# Controller.net
KiCad netlist of a schematic drawn in Altium Designer
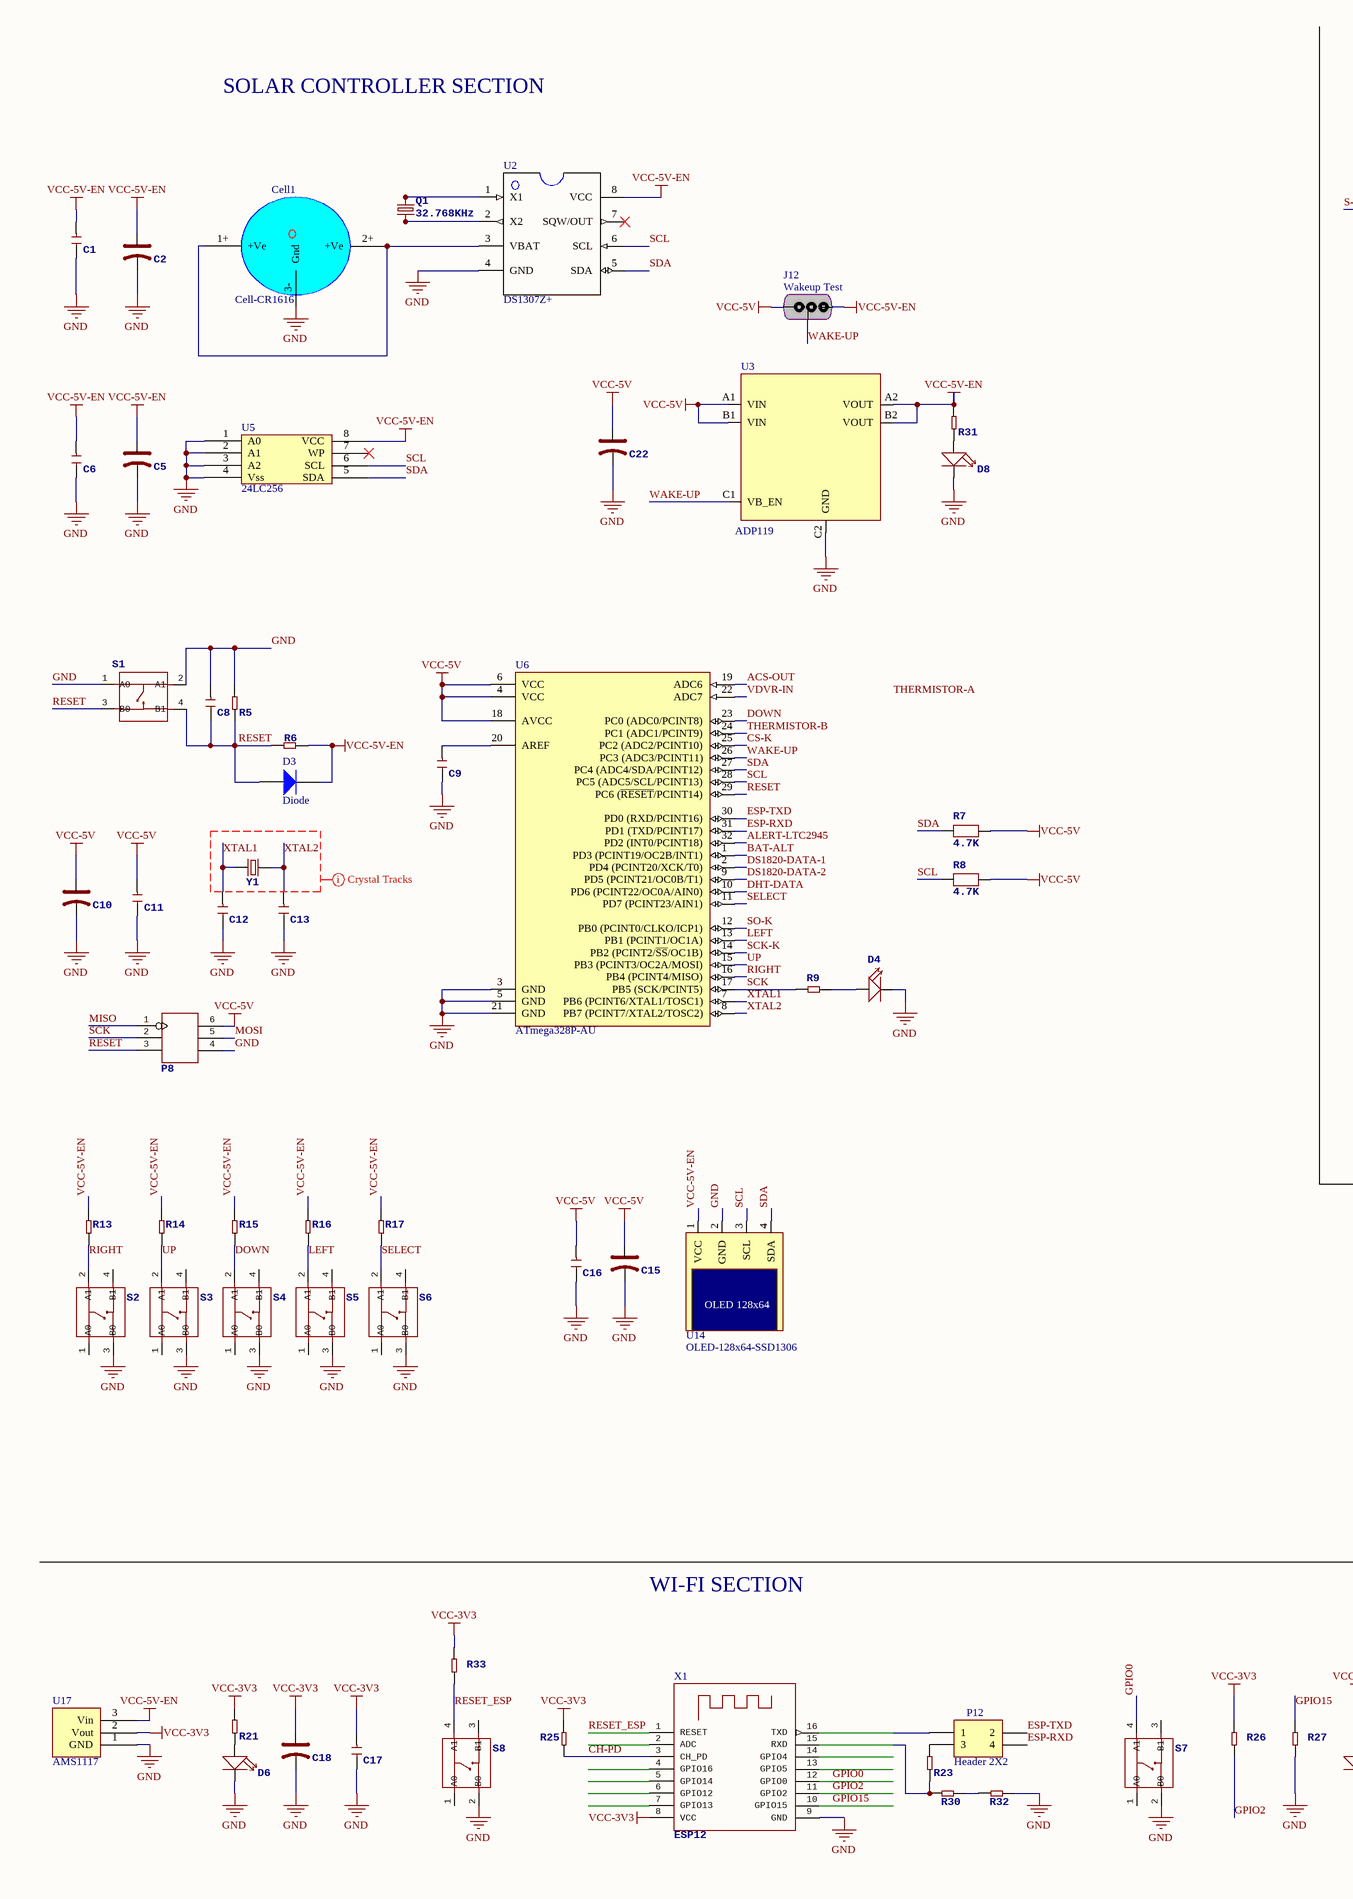
[diagram p0: Controller.SchDoc, left]
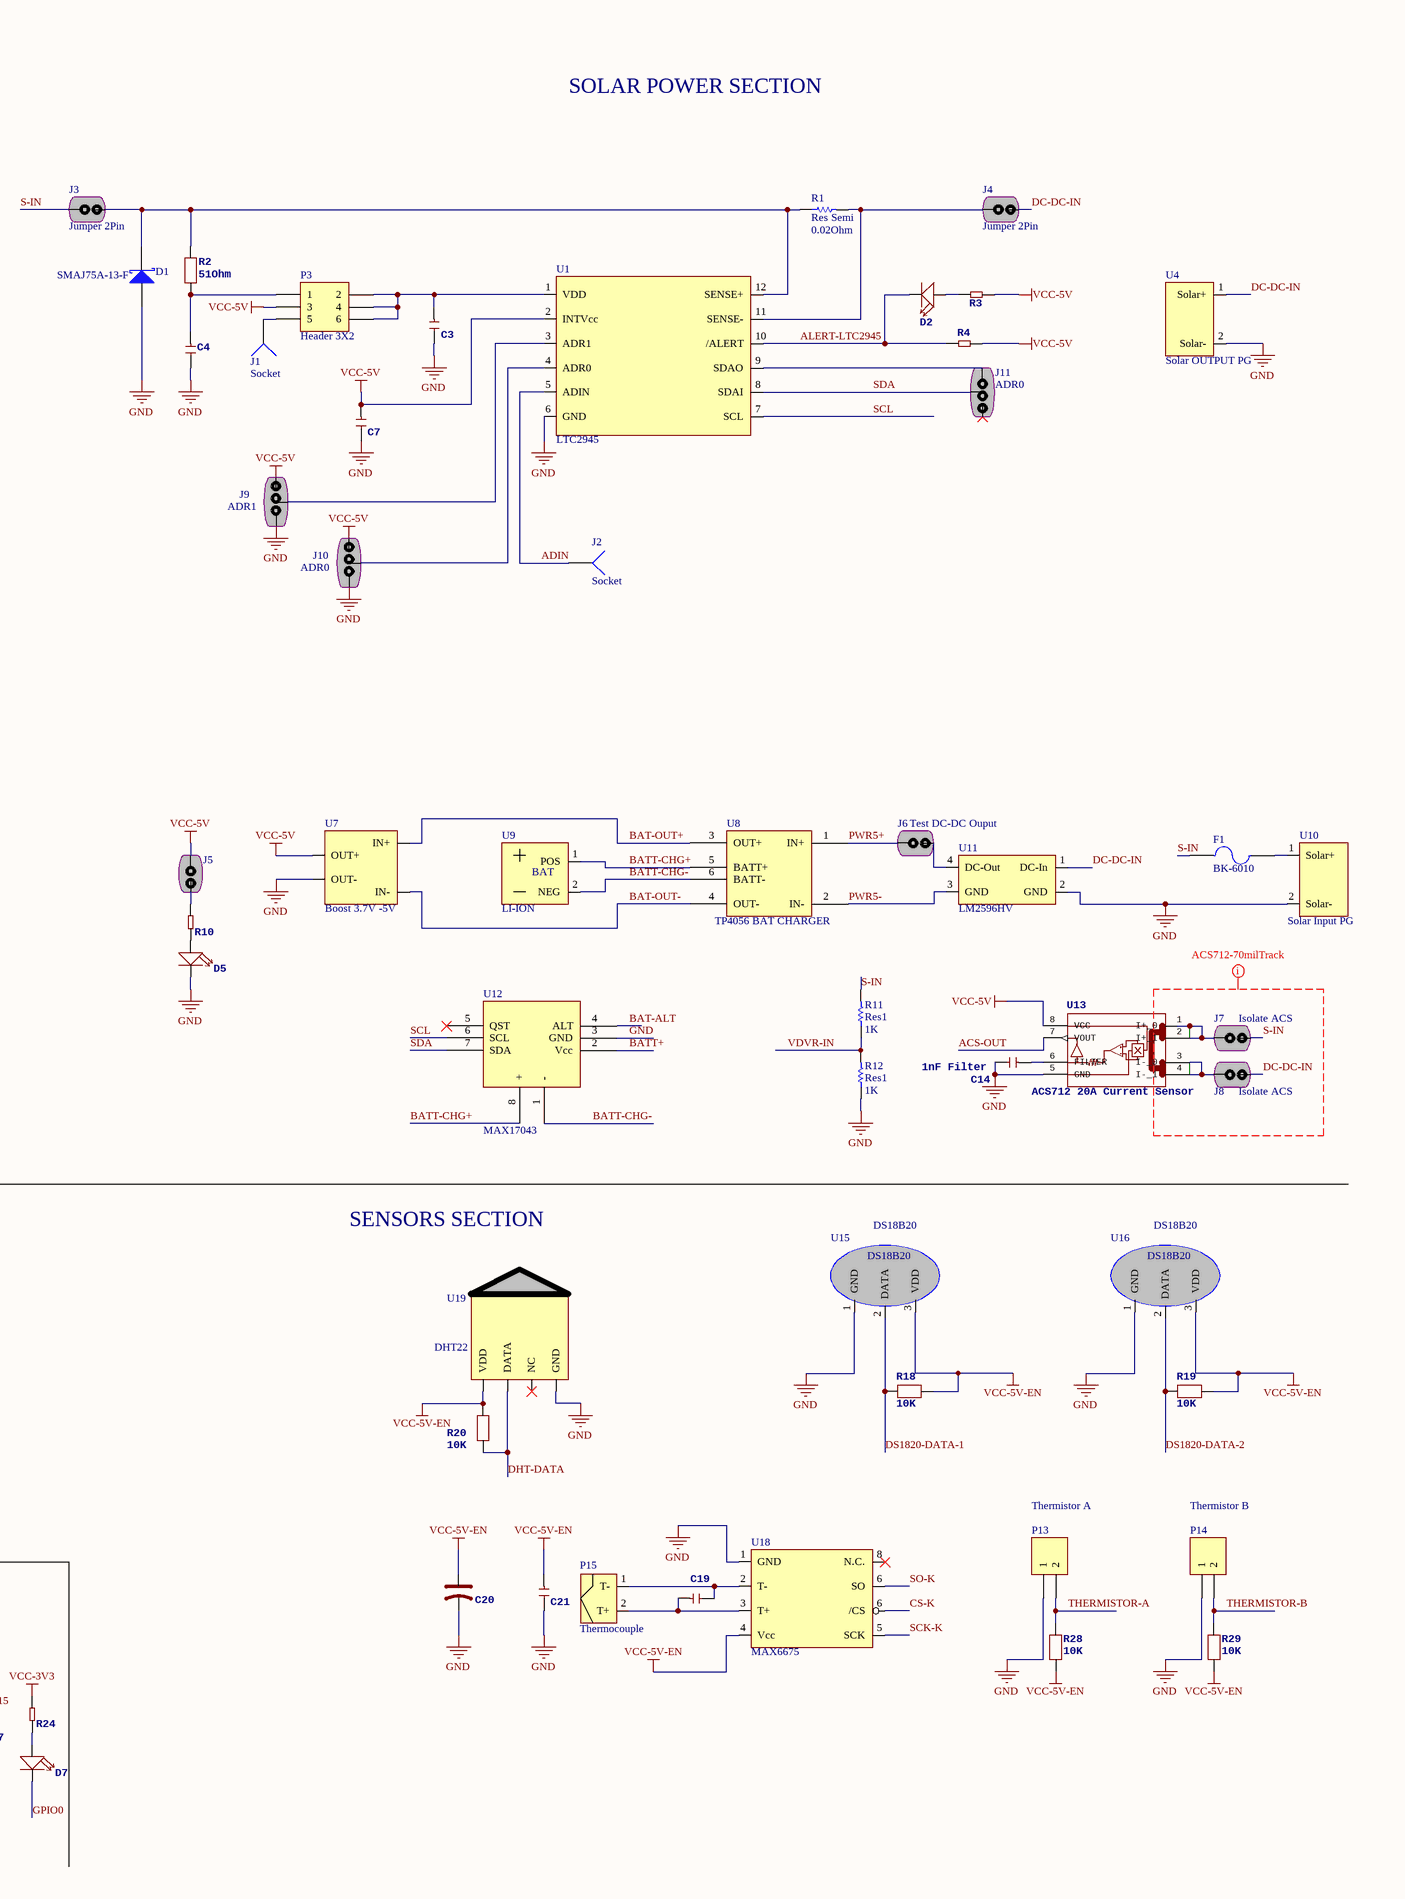
[diagram p1: Controller.SchDoc, right]

(export (version "E")
  (design (tool "Eeschema 10.0.6"))
  (components
    (comp (ref "C1")
      (value "302010165")
      (footprint "C0805")
      (description "100nF")
      (fields (field (name "MPN") "CC0805KRX7R9BB104"))
      (libsource (lib "Seeed-Capacitor") (part "CERAMIC-100NF-50V-10%-X7R(0805)"))
    )
    (comp (ref "C2")
      (value "302020002")
      (footprint "AVX-A")
      (description "10uF Cap Decoupling 16V")
      (fields (field (name "MPN") "TAJA106K016RNJ"))
      (libsource (lib "Seeed-Capacitor") (part "TANTALUM-SMD-10UF-16V-10%(AVX-A)"))
    )
    (comp (ref "C3")
      (value "302010165")
      (footprint "C0805")
      (description "100nF")
      (fields (field (name "MPN") "CC0805KRX7R9BB104"))
      (libsource (lib "Seeed-Capacitor") (part "CERAMIC-100NF-50V-10%-X7R(0805)"))
    )
    (comp (ref "C4")
      (value "302010189")
      (footprint "C1206")
      (fields (field (name "MPN") "CC1206KKX7RCBB102"))
      (libsource (lib "Seeed-Capacitor") (part "CERAMIC-1NF-1KV-10%-X7R?(1206)"))
    )
    (comp (ref "C5")
      (value "302020002")
      (footprint "AVX-A")
      (description "10uF Cap Decoupling 16V")
      (fields (field (name "MPN") "TAJA106K016RNJ"))
      (libsource (lib "Seeed-Capacitor") (part "TANTALUM-SMD-10UF-16V-10%(AVX-A)"))
    )
    (comp (ref "C6")
      (value "302010165")
      (footprint "C0805")
      (description "100nF")
      (fields (field (name "MPN") "CC0805KRX7R9BB104"))
      (libsource (lib "Seeed-Capacitor") (part "CERAMIC-100NF-50V-10%-X7R(0805)"))
    )
    (comp (ref "C7")
      (value "302010165")
      (footprint "C0805")
      (description "100nF")
      (fields (field (name "MPN") "CC0805KRX7R9BB104"))
      (libsource (lib "Seeed-Capacitor") (part "CERAMIC-100NF-50V-10%-X7R(0805)"))
    )
    (comp (ref "C8")
      (value "302010165")
      (footprint "C0805")
      (description "100nF")
      (fields (field (name "MPN") "CC0805KRX7R9BB104"))
      (libsource (lib "Seeed-Capacitor") (part "CERAMIC-100NF-50V-10%-X7R(0805)"))
    )
    (comp (ref "C9")
      (value "302010165")
      (footprint "C0805")
      (description "100nF")
      (fields (field (name "MPN") "CC0805KRX7R9BB104"))
      (libsource (lib "Seeed-Capacitor") (part "CERAMIC-100NF-50V-10%-X7R(0805)"))
    )
    (comp (ref "C10")
      (value "302020002")
      (footprint "AVX-A")
      (description "10uF Cap Decoupling 16V")
      (fields (field (name "MPN") "TAJA106K016RNJ"))
      (libsource (lib "Seeed-Capacitor") (part "TANTALUM-SMD-10UF-16V-10%(AVX-A)"))
    )
    (comp (ref "C11")
      (value "302010165")
      (footprint "C0805")
      (description "100nF")
      (fields (field (name "MPN") "CC0805KRX7R9BB104"))
      (libsource (lib "Seeed-Capacitor") (part "CERAMIC-100NF-50V-10%-X7R(0805)"))
    )
    (comp (ref "C12")
      (value "302010018")
      (footprint "C0805")
      (fields (field (name "MPN") "CC0402JRNPO9BN220"))
      (libsource (lib "Seeed-Capacitor") (part "CERAMIC-22PF-50V-5%-NPO(0402)"))
    )
    (comp (ref "C13")
      (value "302010018")
      (footprint "C0805")
      (fields (field (name "MPN") "CC0402JRNPO9BN220"))
      (libsource (lib "Seeed-Capacitor") (part "CERAMIC-22PF-50V-5%-NPO(0402)"))
    )
    (comp (ref "C14")
      (value "1nF Filter")
      (footprint "C0805")
      (description "1nF Filter Cap as per Datasheet")
      (fields (field (name "MPN") "CC0402KRX7R8BB104"))
      (libsource (lib "Seeed-Capacitor") (part "CERAMIC-100NF-25V-10%-X7R(0402)"))
    )
    (comp (ref "C15")
      (value "302020002")
      (footprint "AVX-A")
      (description "10uF Cap Decoupling 16V")
      (fields (field (name "MPN") "TAJA106K016RNJ"))
      (libsource (lib "Seeed-Capacitor") (part "TANTALUM-SMD-10UF-16V-10%(AVX-A)"))
    )
    (comp (ref "C16")
      (value "302010165")
      (footprint "C0805")
      (description "100nF")
      (fields (field (name "MPN") "CC0805KRX7R9BB104"))
      (libsource (lib "Seeed-Capacitor") (part "CERAMIC-100NF-50V-10%-X7R(0805)"))
    )
    (comp (ref "C17")
      (value "302010165")
      (footprint "C0805")
      (description "100nF")
      (fields (field (name "MPN") "CC0805KRX7R9BB104"))
      (libsource (lib "Seeed-Capacitor") (part "CERAMIC-100NF-50V-10%-X7R(0805)"))
    )
    (comp (ref "C18")
      (value "302020002")
      (footprint "AVX-A")
      (description "10uF Cap Decoupling 16V")
      (fields (field (name "MPN") "TAJA106K016RNJ"))
      (libsource (lib "Seeed-Capacitor") (part "TANTALUM-SMD-10UF-16V-10%(AVX-A)"))
    )
    (comp (ref "C19")
      (value "302010175")
      (footprint "C0805")
      (fields (field (name "MPN") "CC0805JRX7R9BB103"))
      (libsource (lib "Seeed-Capacitor") (part "CERAMIC-10NF-50V-5%-X7R(0805)"))
    )
    (comp (ref "C20")
      (value "302020002")
      (footprint "AVX-A")
      (description "10uF Cap Decoupling 16V")
      (fields (field (name "MPN") "TAJA106K016RNJ"))
      (libsource (lib "Seeed-Capacitor") (part "TANTALUM-SMD-10UF-16V-10%(AVX-A)"))
    )
    (comp (ref "C21")
      (value "302010165")
      (footprint "C0805")
      (description "100nF")
      (fields (field (name "MPN") "CC0805KRX7R9BB104"))
      (libsource (lib "Seeed-Capacitor") (part "CERAMIC-100NF-50V-10%-X7R(0805)"))
    )
    (comp (ref "C22")
      (value "302020002")
      (footprint "AVX-A")
      (description "10uF Cap Decoupling 16V")
      (fields (field (name "MPN") "TAJA106K016RNJ"))
      (libsource (lib "Seeed-Capacitor") (part "TANTALUM-SMD-10UF-16V-10%(AVX-A)"))
    )
    (comp (ref "Cell1")
      (value "Cell-CR1616")
      (footprint "CellCR1616")
      (libsource (lib "Schlib_HAS_1.0") (part "Cell-CR1616"))
    )
    (comp (ref "D1")
      (value "SMAJ75A-13-F")
      (footprint "SMAJ5.0-TVS")
      (description "SMA")
      (fields (field (name "PUBLISHER") "Altium Limited"))
      (libsource (lib "Miscellaneous Devices") (part "D Schottky"))
    )
    (comp (ref "D2")
      (value "304090046")
      (footprint "LED-0805")
      (fields (field (name "MPN") "17-215SURC/S530-A2/TR8"))
      (libsource (lib "Seeed-LED") (part "SMD-LED-CLEAR-RED(0805)"))
    )
    (comp (ref "D3")
      (value "Diode")
      (footprint "1206 Diode SMD")
      (description "Default Diode")
      (fields (field (name "PUBLISHER") "Altium Limited"))
      (libsource (lib "Miscellaneous Devices") (part "Diode"))
    )
    (comp (ref "D4")
      (value "304090046")
      (footprint "LED-0805")
      (fields (field (name "MPN") "17-215SURC/S530-A2/TR8"))
      (libsource (lib "Seeed-LED") (part "SMD-LED-CLEAR-RED(0805)"))
    )
    (comp (ref "D5")
      (value "304090046")
      (footprint "LED-0805")
      (fields (field (name "MPN") "17-215SURC/S530-A2/TR8"))
      (libsource (lib "Seeed-LED") (part "SMD-LED-CLEAR-RED(0805)"))
    )
    (comp (ref "D6")
      (value "304090046")
      (footprint "LED-0805")
      (fields (field (name "MPN") "17-215SURC/S530-A2/TR8"))
      (libsource (lib "Seeed-LED") (part "SMD-LED-CLEAR-RED(0805)"))
    )
    (comp (ref "D7")
      (value "304090046")
      (footprint "LED-0805")
      (fields (field (name "MPN") "17-215SURC/S530-A2/TR8"))
      (libsource (lib "Seeed-LED") (part "SMD-LED-CLEAR-RED(0805)"))
    )
    (comp (ref "D8")
      (value "304090046")
      (footprint "LED-0805")
      (fields (field (name "MPN") "17-215SURC/S530-A2/TR8"))
      (libsource (lib "Seeed-LED") (part "SMD-LED-CLEAR-RED(0805)"))
    )
    (comp (ref "F1")
      (value "BK-6010")
      (footprint "Fuse Block Blade PCB")
      (description "BK-6010, BK-6010-ND,")
      (fields (field (name "PUBLISHER") "Altium Limited"))
      (libsource (lib "Miscellaneous Devices") (part "Fuse 2"))
    )
    (comp (ref "J1")
      (value "Socket")
      (footprint "PIN1")
      (fields (field (name "PUBLISHER") "Altium Limited"))
      (libsource (lib "Miscellaneous Connectors") (part "Socket"))
    )
    (comp (ref "J2")
      (value "Socket")
      (footprint "PIN1")
      (fields (field (name "PUBLISHER") "Altium Limited"))
      (libsource (lib "Miscellaneous Connectors") (part "Socket"))
    )
    (comp (ref "J3")
      (value "Jumper 2Pin")
      (footprint "H2-2.54")
      (description "2.54, Pin header")
      (libsource (lib "Solar_Schlib1") (part "Jumper"))
    )
    (comp (ref "J4")
      (value "Jumper 2Pin")
      (footprint "H2-2.54")
      (description "2.54, Pin header")
      (libsource (lib "Solar_Schlib1") (part "Jumper"))
    )
    (comp (ref "J5")
      (value "Jumper 2Pin")
      (footprint "H2-2.54")
      (description "2.54, Pin header")
      (libsource (lib "Solar_Schlib1") (part "Jumper"))
    )
    (comp (ref "J6")
      (value "Test DC-DC Ouput")
      (footprint "H2-2.54")
      (description "2.54, Pin header")
      (libsource (lib "Solar_Schlib1") (part "Jumper"))
    )
    (comp (ref "J7")
      (value "Isolate ACS")
      (footprint "H2-2.54")
      (description "2.54, Pin header")
      (libsource (lib "Solar_Schlib1") (part "Jumper"))
    )
    (comp (ref "J8")
      (value "Isolate ACS")
      (footprint "H2-2.54")
      (description "2.54, Pin header")
      (libsource (lib "Solar_Schlib1") (part "Jumper"))
    )
    (comp (ref "J9")
      (value "ADR1")
      (footprint "H3-2.54")
      (description "2.54mm Pitch male header")
      (libsource (lib "Solar_Schlib1") (part "Jumper Select"))
    )
    (comp (ref "J10")
      (value "ADR0")
      (footprint "H3-2.54")
      (description "2.54mm Pitch male header")
      (libsource (lib "Solar_Schlib1") (part "Jumper Select"))
    )
    (comp (ref "J11")
      (value "ADR0")
      (footprint "H3-2.54")
      (description "2.54mm Pitch male header")
      (libsource (lib "Solar_Schlib1") (part "Jumper Select"))
    )
    (comp (ref "J12")
      (value "Wakeup Test")
      (footprint "H3-2.54")
      (description "2.54mm Pitch male header")
      (libsource (lib "Solar_Schlib1") (part "Jumper Select"))
    )
    (comp (ref "P3")
      (value "Header 3X2")
      (footprint "HDR2X3")
      (description "Header, 3-Pin, Dual row")
      (fields (field (name "PUBLISHER") "Altium Limited"))
      (libsource (lib "Miscellaneous Connectors") (part "Header 3X2"))
    )
    (comp (ref "P8")
      (value "320020077")
      (footprint "HDR1X6")
      (fields (field (name "MPN") "P125-12A1BS116A1"))
      (libsource (lib "Seeed-Connector") (part "DIP-BLACK-MALE-HEADER(2X3P-2.54）-2.54"))
    )
    (comp (ref "P12")
      (value "Header 2X2")
      (footprint "HDR2X2")
      (description "Header, 2-Pin, Dual row")
      (fields (field (name "PUBLISHER") "Altium Limited"))
      (libsource (lib "Miscellaneous Connectors") (part "Header 2X2"))
    )
    (comp (ref "P13")
      (value "Thermistor A")
      (footprint "HDR1X2")
      (description "Header, 2-Pin")
      (fields (field (name "PUBLISHER") "Altium Limited"))
      (libsource (lib "Miscellaneous Connectors") (part "Header 2"))
    )
    (comp (ref "P14")
      (value "Thermistor B")
      (footprint "HDR1X2")
      (description "Header, 2-Pin")
      (fields (field (name "PUBLISHER") "Altium Limited"))
      (libsource (lib "Miscellaneous Connectors") (part "Header 2"))
    )
    (comp (ref "P15")
      (value "Thermocouple")
      (footprint "ScrewTerminal8.5")
      (description "K Type Termocouple")
      (libsource (lib "Solar_Schlib1") (part "ScrewTerminal8.5"))
    )
    (comp (ref "Q1")
      (value "32.768KHz")
      (footprint "RTC-XTAL")
      (libsource (lib "crystal") (part "CRYTALTC38H"))
    )
    (comp (ref "R1")
      (value "Res Semi")
      (footprint "AXIAL-0.5")
      (description "Semiconductor Resistor")
      (fields (field (name "ALTIUM_VALUE") "0.02Ohm") (field (name "PUBLISHER") "Altium Limited"))
      (libsource (lib "Miscellaneous Devices") (part "Res Semi"))
    )
    (comp (ref "R2")
      (value "51Ohm")
      (footprint "R0805")
      (libsource (lib "microbuilder") (part "RESISTOR0805_NOOUTLINE"))
    )
    (comp (ref "R3")
      (value "301010297")
      (footprint "R0603")
      (fields (field (name "MPN") "RC0603JR-07390RL"))
      (libsource (lib "Seeed-Resistor") (part "SMD-RES-390R-5%-1/10W(0603)"))
    )
    (comp (ref "R4")
      (value "301010361")
      (footprint "R0805")
      (description "10K")
      (fields (field (name "MPN") "RC0805FR-0710KL"))
      (libsource (lib "Seeed-Resistor") (part "SMD-RES-10K-1%-1/8W(0805)"))
    )
    (comp (ref "R5")
      (value "301010006")
      (footprint "R0402")
      (fields (field (name "MPN") "RC0402JR-071KL"))
      (libsource (lib "Seeed-Resistor") (part "SMD-RES-1K-5%-1/16W(0402)"))
    )
    (comp (ref "R6")
      (value "301010361")
      (footprint "R0805")
      (description "Pull up 10K resistor")
      (fields (field (name "MPN") "RC0805FR-0710KL"))
      (libsource (lib "Seeed-Resistor") (part "SMD-RES-10K-1%-1/8W(0805)"))
    )
    (comp (ref "R7")
      (value "4.7K")
      (footprint "R0805")
      (libsource (lib "microbuilder") (part "RESISTOR0805_NOOUTLINE"))
    )
    (comp (ref "R8")
      (value "4.7K")
      (footprint "R0805")
      (libsource (lib "microbuilder") (part "RESISTOR0805_NOOUTLINE"))
    )
    (comp (ref "R9")
      (value "301010297")
      (footprint "R0603")
      (fields (field (name "MPN") "RC0603JR-07390RL"))
      (libsource (lib "Seeed-Resistor") (part "SMD-RES-390R-5%-1/10W(0603)"))
    )
    (comp (ref "R10")
      (value "301010297")
      (footprint "R0603")
      (fields (field (name "MPN") "RC0603JR-07390RL"))
      (libsource (lib "Seeed-Resistor") (part "SMD-RES-390R-5%-1/10W(0603)"))
    )
    (comp (ref "R11")
      (value "Res1")
      (footprint "AXIAL-0.3")
      (description "Resistor")
      (fields (field (name "ALTIUM_VALUE") "1K") (field (name "PUBLISHER") "Altium Limited"))
      (libsource (lib "Miscellaneous Devices") (part "Res1"))
    )
    (comp (ref "R12")
      (value "Res1")
      (footprint "AXIAL-0.3")
      (description "Resistor")
      (fields (field (name "ALTIUM_VALUE") "1K") (field (name "PUBLISHER") "Altium Limited"))
      (libsource (lib "Miscellaneous Devices") (part "Res1"))
    )
    (comp (ref "R13")
      (value "301010361")
      (footprint "R0805")
      (description "Pull up 10K resistor for button")
      (fields (field (name "MPN") "RC0805FR-0710KL"))
      (libsource (lib "Seeed-Resistor") (part "SMD-RES-10K-1%-1/8W(0805)"))
    )
    (comp (ref "R14")
      (value "301010361")
      (footprint "R0805")
      (description "Pull up 10K resistor for button")
      (fields (field (name "MPN") "RC0805FR-0710KL"))
      (libsource (lib "Seeed-Resistor") (part "SMD-RES-10K-1%-1/8W(0805)"))
    )
    (comp (ref "R15")
      (value "301010361")
      (footprint "R0805")
      (description "Pull up 10K resistor for button")
      (fields (field (name "MPN") "RC0805FR-0710KL"))
      (libsource (lib "Seeed-Resistor") (part "SMD-RES-10K-1%-1/8W(0805)"))
    )
    (comp (ref "R16")
      (value "301010361")
      (footprint "R0805")
      (description "Pull up 10K resistor for button")
      (fields (field (name "MPN") "RC0805FR-0710KL"))
      (libsource (lib "Seeed-Resistor") (part "SMD-RES-10K-1%-1/8W(0805)"))
    )
    (comp (ref "R17")
      (value "301010361")
      (footprint "R0805")
      (description "Pull up 10K resistor for button")
      (fields (field (name "MPN") "RC0805FR-0710KL"))
      (libsource (lib "Seeed-Resistor") (part "SMD-RES-10K-1%-1/8W(0805)"))
    )
    (comp (ref "R18")
      (value "10K")
      (footprint "R0805")
      (libsource (lib "microbuilder") (part "RESISTOR0805_NOOUTLINE"))
    )
    (comp (ref "R19")
      (value "10K")
      (footprint "R0805")
      (libsource (lib "microbuilder") (part "RESISTOR0805_NOOUTLINE"))
    )
    (comp (ref "R20")
      (value "10K")
      (footprint "R0805")
      (libsource (lib "microbuilder") (part "RESISTOR0805_NOOUTLINE"))
    )
    (comp (ref "R21")
      (value "301010297")
      (footprint "R0603")
      (fields (field (name "MPN") "RC0603JR-07390RL"))
      (libsource (lib "Seeed-Resistor") (part "SMD-RES-390R-5%-1/10W(0603)"))
    )
    (comp (ref "R23")
      (value "301010311")
      (footprint "R0805")
      (fields (field (name "MPN") "RC0805JR-071KL"))
      (libsource (lib "Seeed-Resistor") (part "SMD-RES-1K-5%-1/8W(0805)"))
    )
    (comp (ref "R24")
      (value "301010297")
      (footprint "R0603")
      (fields (field (name "MPN") "RC0603JR-07390RL"))
      (libsource (lib "Seeed-Resistor") (part "SMD-RES-390R-5%-1/10W(0603)"))
    )
    (comp (ref "R25")
      (value "301010361")
      (footprint "R0805")
      (description "Pull up 10K resistor for button")
      (fields (field (name "MPN") "RC0805FR-0710KL"))
      (libsource (lib "Seeed-Resistor") (part "SMD-RES-10K-1%-1/8W(0805)"))
    )
    (comp (ref "R26")
      (value "301010361")
      (footprint "R0805")
      (description "Pull up 10K resistor for button")
      (fields (field (name "MPN") "RC0805FR-0710KL"))
      (libsource (lib "Seeed-Resistor") (part "SMD-RES-10K-1%-1/8W(0805)"))
    )
    (comp (ref "R27")
      (value "301010361")
      (footprint "R0805")
      (description "Pull up 10K resistor for button")
      (fields (field (name "MPN") "RC0805FR-0710KL"))
      (libsource (lib "Seeed-Resistor") (part "SMD-RES-10K-1%-1/8W(0805)"))
    )
    (comp (ref "R28")
      (value "10K")
      (footprint "R0805")
      (libsource (lib "microbuilder") (part "RESISTOR0805_NOOUTLINE"))
    )
    (comp (ref "R29")
      (value "10K")
      (footprint "R0805")
      (libsource (lib "microbuilder") (part "RESISTOR0805_NOOUTLINE"))
    )
    (comp (ref "R30")
      (value "301010311")
      (footprint "R0805")
      (fields (field (name "MPN") "RC0805JR-071KL"))
      (libsource (lib "Seeed-Resistor") (part "SMD-RES-1K-5%-1/8W(0805)"))
    )
    (comp (ref "R31")
      (value "301010297")
      (footprint "R0603")
      (fields (field (name "MPN") "RC0603JR-07390RL"))
      (libsource (lib "Seeed-Resistor") (part "SMD-RES-390R-5%-1/10W(0603)"))
    )
    (comp (ref "R32")
      (value "301010311")
      (footprint "R0805")
      (fields (field (name "MPN") "RC0805JR-071KL"))
      (libsource (lib "Seeed-Resistor") (part "SMD-RES-1K-5%-1/8W(0805)"))
    )
    (comp (ref "R33")
      (value "301010361")
      (footprint "R0805")
      (description "Pull up 10K resistor for button")
      (fields (field (name "MPN") "RC0805FR-0710KL"))
      (libsource (lib "Seeed-Resistor") (part "SMD-RES-10K-1%-1/8W(0805)"))
    )
    (comp (ref "S1")
      (value "311020017")
      (footprint "SW4-SMD-5.2X5.2X1.5MM")
      (fields (field (name "MPN") "SKQGADE010"))
      (libsource (lib "Seeed-Switch") (part "SMD-BUTTON(4P-5.2X5.2X1.5MM-SKQGADE010)-SKQGADE010"))
    )
    (comp (ref "S2")
      (value "311020017")
      (footprint "SW4-SMD-5.2X5.2X1.5MM")
      (fields (field (name "MPN") "SKQGADE010"))
      (libsource (lib "Seeed-Switch") (part "SMD-BUTTON(4P-5.2X5.2X1.5MM-SKQGADE010)-SKQGADE010"))
    )
    (comp (ref "S3")
      (value "311020017")
      (footprint "SW4-SMD-5.2X5.2X1.5MM")
      (fields (field (name "MPN") "SKQGADE010"))
      (libsource (lib "Seeed-Switch") (part "SMD-BUTTON(4P-5.2X5.2X1.5MM-SKQGADE010)-SKQGADE010"))
    )
    (comp (ref "S4")
      (value "311020017")
      (footprint "SW4-SMD-5.2X5.2X1.5MM")
      (fields (field (name "MPN") "SKQGADE010"))
      (libsource (lib "Seeed-Switch") (part "SMD-BUTTON(4P-5.2X5.2X1.5MM-SKQGADE010)-SKQGADE010"))
    )
    (comp (ref "S5")
      (value "311020017")
      (footprint "SW4-SMD-5.2X5.2X1.5MM")
      (fields (field (name "MPN") "SKQGADE010"))
      (libsource (lib "Seeed-Switch") (part "SMD-BUTTON(4P-5.2X5.2X1.5MM-SKQGADE010)-SKQGADE010"))
    )
    (comp (ref "S6")
      (value "311020017")
      (footprint "SW4-SMD-5.2X5.2X1.5MM")
      (fields (field (name "MPN") "SKQGADE010"))
      (libsource (lib "Seeed-Switch") (part "SMD-BUTTON(4P-5.2X5.2X1.5MM-SKQGADE010)-SKQGADE010"))
    )
    (comp (ref "S7")
      (value "311020004")
      (footprint "SW4-SMD-6.0X6.0X5.0MM")
      (fields (field (name "MPN") "DTSM-62K-S-V-T/R(SN431)"))
      (libsource (lib "Seeed-Switch") (part "SMD-SWITCH-TACTILE-SPST-NO(4P-D6.0MM)"))
    )
    (comp (ref "S8")
      (value "311020004")
      (footprint "SW4-SMD-6.0X6.0X5.0MM")
      (fields (field (name "MPN") "DTSM-62K-S-V-T/R(SN431)"))
      (libsource (lib "Seeed-Switch") (part "SMD-SWITCH-TACTILE-SPST-NO(4P-D6.0MM)"))
    )
    (comp (ref "U1")
      (value "LTC2945")
      (footprint "LTC2945")
      (description "V I P Monitor I2C Interface")
      (libsource (lib "Solar_Schlib1") (part "LTC2945"))
    )
    (comp (ref "U2")
      (value "DS1307Z+")
      (footprint "SO08")
      (description "RTC circuit%3B I2C%3B NV SRAM%3B 56B%3B 4.5%C3%B75.5VDC%3B SO8")
      (fields (field (name "MF") "Maxim Integrated"))
      (libsource (lib "DS1307Z_") (part "DS1307Z+"))
    )
    (comp (ref "U3") (value "ADP119") (footprint "BGA3x2") (libsource (lib "Solar_Schlib1") (part "ADP119")))
    (comp (ref "U4")
      (value "Solar OUTPUT PG")
      (footprint "SCREW TERMINAL")
      (libsource (lib "") (part "PG_IN_1"))
    )
    (comp (ref "U5") (value "24LC256") (footprint "SO08") (libsource (lib "Schlib_HAS_1.0") (part "24LC256")))
    (comp (ref "U6")
      (value "ATmega328P-AU")
      (footprint "TQFP32-0.8-7X7MM")
      (fields (field (name "PUBLISHER") "Altium Limited"))
      (libsource (lib "Atmel Microcontroller 8-Bit megaAVR") (part "ATmega328P-AU"))
    )
    (comp (ref "U7")
      (value "Boost 3.7V -5V")
      (footprint "Boost Cov")
      (description "Boost converter module from Cell to 5V")
      (libsource (lib "Solar_Schlib1") (part "Boost-3.7V-5V"))
    )
    (comp (ref "U8")
      (value "TP4056 BAT CHARGER")
      (footprint "TP4056")
      (description "TP4056 Module")
      (libsource (lib "eSizeSchLIB") (part "TP4056"))
    )
    (comp (ref "U9")
      (value "LI-ION")
      (footprint "Cell-Holder")
      (description "Li Ion Battery 3.7V")
      (libsource (lib "Solar_Schlib1") (part "Battery"))
    )
    (comp (ref "U10")
      (value "Solar Input PG")
      (footprint "SCREW TERMINAL")
      (libsource (lib "Solar_Schlib1") (part "PG_IN"))
    )
    (comp (ref "U11")
      (value "LM2596HV")
      (footprint "LM2596HVS DC-DC step-down module")
      (description "DC DC Adjustable Buck converter input upto 60V")
      (libsource (lib "Solar_Schlib1") (part "LM2596HV"))
    )
    (comp (ref "U12")
      (value "MAX17043")
      (footprint "MAX17043")
      (description "Battery Fuel Guage")
      (libsource (lib "eSizeSchLIB") (part "MAX17043"))
    )
    (comp (ref "U13")
      (value "ACS712 20A Current Sensor")
      (footprint "SO08")
      (libsource (lib "ACS712") (part "ACS712"))
    )
    (comp (ref "U14")
      (value "OLED-128x64-SSD1306")
      (footprint "OLED-128x64")
      (description "OLED Display OLED-128x64-SSD1306")
      (libsource (lib "Solar_Schlib1") (part "OLED-128x64-SSD1306"))
    )
    (comp (ref "U15")
      (value "DS18B20")
      (footprint "TO-92")
      (description "On Board Temperature Sensor")
      (libsource (lib "Solar_Schlib1") (part "DS18B20"))
    )
    (comp (ref "U16")
      (value "DS18B20")
      (footprint "TO-92")
      (description "On Board Temperature Sensor")
      (libsource (lib "Solar_Schlib1") (part "DS18B20"))
    )
    (comp (ref "U17")
      (value "AMS1117")
      (footprint "AMS1117-3.3")
      (description "3.3V Regulator")
      (libsource (lib "eSizeSchLIB") (part "AMS1117"))
    )
    (comp (ref "U18")
      (value "MAX6675")
      (footprint "SO8_N")
      (description "K-Thermocoupleto-Digital  Converter")
      (libsource (lib "Solar_Schlib1") (part "MAX6675"))
    )
    (comp (ref "U19")
      (value "DHT22")
      (footprint "DHT22_AM2303_HORIZ")
      (description "Temperature and Humidity Sensor")
      (libsource (lib "Solar_Schlib1") (part "DHT22"))
    )
    (comp (ref "X1")
      (value "ESP-12")
      (footprint "ESP8266-12E")
      (fields (field (name "ESP12") "ESP12"))
      (libsource (lib "microbuilder") (part "ESP-12"))
    )
    (comp (ref "Y1")
      (value "306010054")
      (footprint "SMT_XTAL")
      (fields (field (name "MPN") "X053201602002"))
      (libsource (lib "Seeed-Crystal Oscillator") (part "SMD-CRYSTAL-16MHZ-8PF-20PPM-40R(2P-5.0X3.2MM)"))
    )
  )
  (nets
    (net (code "1") (name "/ACS-OUT") (class "Default")
      (node (ref "U13") (pin "7") (pinfunction "VOUT_7") (pintype "output"))
      (node (ref "U6") (pin "19") (pinfunction "ADC6_19") (pintype "input"))
    )
    (net (code "2") (name "/ADIN") (class "Default")
      (node (ref "J2") (pin "1") (pinfunction "1_1") (pintype "passive"))
      (node (ref "U1") (pin "5") (pinfunction "ADIN_5") (pintype "power_in"))
    )
    (net (code "3") (name "/ALERT-LTC2945") (class "Default")
      (node (ref "D2") (pin "-") (pinfunction "-_-") (pintype "passive"))
      (node (ref "R4") (pin "1") (pinfunction "1_1") (pintype "passive"))
      (node (ref "U1") (pin "10") (pinfunction "/ALERT_10") (pintype "power_in"))
      (node (ref "U6") (pin "32") (pinfunction "PD2_(INT0/PCINT18)_32") (pintype "bidirectional"))
    )
    (net (code "4") (name "/BAT-ALT") (class "Default")
      (node (ref "U12") (pin "4") (pinfunction "ALT_4") (pintype "passive"))
      (node (ref "U6") (pin "1") (pinfunction "PD3_(PCINT19/OC2B/INT1)_1") (pintype "bidirectional"))
    )
    (net (code "5") (name "/BAT-OUT+") (class "Default")
      (node (ref "U7") (pin "IN+") (pinfunction "IN+_IN+") (pintype "power_in"))
      (node (ref "U8") (pin "3") (pinfunction "OUT+_3") (pintype "power_in"))
    )
    (net (code "6") (name "/BAT-OUT-") (class "Default")
      (node (ref "U7") (pin "IN-") (pinfunction "IN-_IN-") (pintype "power_in"))
      (node (ref "U8") (pin "4") (pinfunction "OUT-_4") (pintype "power_in"))
    )
    (net (code "7") (name "/BATT+") (class "Default")
      (node (ref "U12") (pin "2") (pinfunction "Vcc_2") (pintype "passive"))
    )
    (net (code "8") (name "/BATT-CHG+") (class "Default")
      (node (ref "U12") (pin "8") (pinfunction "+_8") (pintype "passive"))
      (node (ref "U8") (pin "5") (pinfunction "BATT+_5") (pintype "power_in"))
      (node (ref "U9") (pin "1") (pinfunction "POS_1") (pintype "power_in"))
    )
    (net (code "9") (name "/BATT-CHG-") (class "Default")
      (node (ref "U12") (pin "1") (pinfunction "-_1") (pintype "passive"))
      (node (ref "U8") (pin "6") (pinfunction "BATT-_6") (pintype "power_in"))
      (node (ref "U9") (pin "2") (pinfunction "NEG_2") (pintype "power_in"))
    )
    (net (code "10") (name "/CH-PD") (class "Default")
      (node (ref "R25") (pin "1") (pinfunction "1_1") (pintype "passive"))
      (node (ref "X1") (pin "3") (pinfunction "CH_PD_3") (pintype "passive"))
    )
    (net (code "11") (name "/CS-K") (class "Default")
      (node (ref "U18") (pin "6") (pinfunction "/CS_6") (pintype "power_in"))
      (node (ref "U6") (pin "25") (pinfunction "PC2_(ADC2/PCINT10)_25") (pintype "bidirectional"))
    )
    (net (code "12") (name "/DC-DC-IN") (class "Default")
      (node (ref "J4") (pin "1") (pinfunction "1_1") (pintype "power_in"))
      (node (ref "J8") (pin "1") (pinfunction "1_1") (pintype "power_in"))
      (node (ref "U11") (pin "1") (pinfunction "DC-In_1") (pintype "power_in"))
      (node (ref "U4") (pin "1") (pinfunction "Solar+_1") (pintype "power_in"))
    )
    (net (code "13") (name "/DHT-DATA") (class "Default")
      (node (ref "R20") (pin "1") (pinfunction "1_1") (pintype "passive"))
      (node (ref "U19") (pin "DATA") (pinfunction "DATA_DATA") (pintype "power_in"))
      (node (ref "U6") (pin "10") (pinfunction "PD6_(PCINT22/OC0A/AIN0)_10") (pintype "bidirectional"))
    )
    (net (code "14") (name "/DOWN") (class "Default")
      (node (ref "R15") (pin "1") (pinfunction "1_1") (pintype "passive"))
      (node (ref "S4") (pin "2") (pinfunction "A1_2") (pintype "passive"))
      (node (ref "U6") (pin "23") (pinfunction "PC0_(ADC0/PCINT8)_23") (pintype "bidirectional"))
    )
    (net (code "15") (name "/DS1820-DATA-1") (class "Default")
      (node (ref "R18") (pin "2") (pinfunction "2_2") (pintype "passive"))
      (node (ref "U15") (pin "2") (pinfunction "DATA_2") (pintype "power_in"))
      (node (ref "U6") (pin "2") (pinfunction "PD4_(PCINT20/XCK/T0)_2") (pintype "bidirectional"))
    )
    (net (code "16") (name "/DS1820-DATA-2") (class "Default")
      (node (ref "R19") (pin "2") (pinfunction "2_2") (pintype "passive"))
      (node (ref "U16") (pin "2") (pinfunction "DATA_2") (pintype "power_in"))
      (node (ref "U6") (pin "9") (pinfunction "PD5_(PCINT21/OC0B/T1)_9") (pintype "bidirectional"))
    )
    (net (code "17") (name "/ESP-RXD") (class "Default")
      (node (ref "P12") (pin "4") (pinfunction "4_4") (pintype "passive"))
      (node (ref "U6") (pin "31") (pinfunction "PD1_(TXD/PCINT17)_31") (pintype "bidirectional"))
    )
    (net (code "18") (name "/ESP-TXD") (class "Default")
      (node (ref "P12") (pin "2") (pinfunction "2_2") (pintype "passive"))
      (node (ref "U6") (pin "30") (pinfunction "PD0_(RXD/PCINT16)_30") (pintype "bidirectional"))
    )
    (net (code "19") (name "/GPIO0") (class "Default")
      (node (ref "D7") (pin "-") (pinfunction "-_-") (pintype "passive"))
      (node (ref "S7") (pin "4") (pinfunction "A1_4") (pintype "passive"))
      (node (ref "X1") (pin "12") (pinfunction "GPIO0_12") (pintype "passive"))
    )
    (net (code "20") (name "/GPIO2") (class "Default")
      (node (ref "R26") (pin "1") (pinfunction "1_1") (pintype "passive"))
      (node (ref "X1") (pin "11") (pinfunction "GPIO2_11") (pintype "passive"))
    )
    (net (code "21") (name "/GPIO15") (class "Default")
      (node (ref "R27") (pin "2") (pinfunction "2_2") (pintype "passive"))
      (node (ref "X1") (pin "10") (pinfunction "GPIO15_10") (pintype "passive"))
    )
    (net (code "22") (name "/LEFT") (class "Default")
      (node (ref "R16") (pin "1") (pinfunction "1_1") (pintype "passive"))
      (node (ref "S5") (pin "2") (pinfunction "A1_2") (pintype "passive"))
      (node (ref "U6") (pin "13") (pinfunction "PB1_(PCINT1/OC1A)_13") (pintype "bidirectional"))
    )
    (net (code "23") (name "/MISO") (class "Default")
      (node (ref "P8") (pin "1") (pinfunction "1_1") (pintype "passive"))
    )
    (net (code "24") (name "/MOSI") (class "Default")
      (node (ref "P8") (pin "5") (pinfunction "5_5") (pintype "passive"))
    )
    (net (code "25") (name "/PWR5+") (class "Default")
      (node (ref "J6") (pin "2") (pinfunction "2_2") (pintype "power_in"))
      (node (ref "U8") (pin "1") (pinfunction "IN+_1") (pintype "power_in"))
    )
    (net (code "26") (name "/PWR5-") (class "Default")
      (node (ref "U11") (pin "3") (pinfunction "GND_3") (pintype "power_in"))
      (node (ref "U8") (pin "2") (pinfunction "IN-_2") (pintype "power_in"))
    )
    (net (code "27") (name "/RESET") (class "Default")
      (node (ref "C8") (pin "1") (pinfunction "1_1") (pintype "passive"))
      (node (ref "D3") (pin "1") (pinfunction "A_1") (pintype "passive"))
      (node (ref "P8") (pin "3") (pinfunction "3_3") (pintype "passive"))
      (node (ref "R5") (pin "2") (pinfunction "2_2") (pintype "passive"))
      (node (ref "R6") (pin "2") (pinfunction "2_2") (pintype "passive"))
      (node (ref "S1") (pin "3") (pinfunction "B0_3") (pintype "passive"))
      (node (ref "S1") (pin "4") (pinfunction "B1_4") (pintype "passive"))
      (node (ref "U6") (pin "29") (pinfunction "PC6_(~{RESET}/PCINT14)_29") (pintype "bidirectional"))
    )
    (net (code "28") (name "/RESET_ESP") (class "Default")
      (node (ref "R33") (pin "1") (pinfunction "1_1") (pintype "passive"))
      (node (ref "S8") (pin "4") (pinfunction "A1_4") (pintype "passive"))
      (node (ref "X1") (pin "1") (pinfunction "RESET_1") (pintype "passive"))
    )
    (net (code "29") (name "/RIGHT") (class "Default")
      (node (ref "R13") (pin "1") (pinfunction "1_1") (pintype "passive"))
      (node (ref "S2") (pin "2") (pinfunction "A1_2") (pintype "passive"))
      (node (ref "U6") (pin "16") (pinfunction "PB4_(PCINT4/MISO)_16") (pintype "bidirectional"))
    )
    (net (code "30") (name "/S-IN") (class "Default")
      (node (ref "F1") (pin "1") (pinfunction "1_1") (pintype "passive"))
      (node (ref "J3") (pin "2") (pinfunction "2_2") (pintype "power_in"))
      (node (ref "J7") (pin "1") (pinfunction "1_1") (pintype "power_in"))
      (node (ref "R11") (pin "2") (pinfunction "2_2") (pintype "passive"))
    )
    (net (code "31") (name "/SCK") (class "Default")
      (node (ref "P8") (pin "2") (pinfunction "2_2") (pintype "passive"))
      (node (ref "R9") (pin "1") (pinfunction "1_1") (pintype "passive"))
      (node (ref "U6") (pin "17") (pinfunction "PB5_(SCK/PCINT5)_17") (pintype "bidirectional"))
    )
    (net (code "32") (name "/SCK-K") (class "Default")
      (node (ref "U18") (pin "5") (pinfunction "SCK_5") (pintype "power_in"))
      (node (ref "U6") (pin "14") (pinfunction "PB2_(PCINT2/~{SS}/OC1B)_14") (pintype "bidirectional"))
    )
    (net (code "33") (name "/SCL") (class "Default")
      (node (ref "R8") (pin "1") (pinfunction "1_1") (pintype "passive"))
      (node (ref "U1") (pin "7") (pinfunction "SCL_7") (pintype "power_in"))
      (node (ref "U12") (pin "6") (pinfunction "SCL_6") (pintype "passive"))
      (node (ref "U14") (pin "3") (pinfunction "SCL_3") (pintype "power_in"))
      (node (ref "U2") (pin "6") (pinfunction "SCL_6") (pintype "input"))
      (node (ref "U5") (pin "6") (pinfunction "SCL_6") (pintype "passive"))
      (node (ref "U6") (pin "28") (pinfunction "PC5_(ADC5/SCL/PCINT13)_28") (pintype "bidirectional"))
    )
    (net (code "34") (name "/SDA") (class "Default")
      (node (ref "J11") (pin "2") (pinfunction "2_2") (pintype "power_in"))
      (node (ref "R7") (pin "1") (pinfunction "1_1") (pintype "passive"))
      (node (ref "U1") (pin "8") (pinfunction "SDAI_8") (pintype "power_in"))
      (node (ref "U12") (pin "7") (pinfunction "SDA_7") (pintype "passive"))
      (node (ref "U14") (pin "4") (pinfunction "SDA_4") (pintype "power_in"))
      (node (ref "U2") (pin "5") (pinfunction "SDA_5") (pintype "bidirectional"))
      (node (ref "U5") (pin "5") (pinfunction "SDA_5") (pintype "passive"))
      (node (ref "U6") (pin "27") (pinfunction "PC4_(ADC4/SDA/PCINT12)_27") (pintype "bidirectional"))
    )
    (net (code "35") (name "/SELECT") (class "Default")
      (node (ref "R17") (pin "1") (pinfunction "1_1") (pintype "passive"))
      (node (ref "S6") (pin "2") (pinfunction "A1_2") (pintype "passive"))
      (node (ref "U6") (pin "11") (pinfunction "PD7_(PCINT23/AIN1)_11") (pintype "bidirectional"))
    )
    (net (code "36") (name "/SO-K") (class "Default")
      (node (ref "U18") (pin "6") (pinfunction "SO_6") (pintype "power_in"))
      (node (ref "U6") (pin "12") (pinfunction "PB0_(PCINT0/CLKO/ICP1)_12") (pintype "bidirectional"))
    )
    (net (code "37") (name "/THERMISTOR-A") (class "Default")
      (node (ref "P13") (pin "2") (pinfunction "2_2") (pintype "passive"))
      (node (ref "R28") (pin "2") (pinfunction "2_2") (pintype "passive"))
    )
    (net (code "38") (name "/THERMISTOR-B") (class "Default")
      (node (ref "P14") (pin "2") (pinfunction "2_2") (pintype "passive"))
      (node (ref "R29") (pin "2") (pinfunction "2_2") (pintype "passive"))
      (node (ref "U6") (pin "24") (pinfunction "PC1_(ADC1/PCINT9)_24") (pintype "bidirectional"))
    )
    (net (code "39") (name "/UP") (class "Default")
      (node (ref "R14") (pin "1") (pinfunction "1_1") (pintype "passive"))
      (node (ref "S3") (pin "2") (pinfunction "A1_2") (pintype "passive"))
      (node (ref "U6") (pin "15") (pinfunction "PB3_(PCINT3/OC2A/MOSI)_15") (pintype "bidirectional"))
    )
    (net (code "40") (name "/VDVR-IN") (class "Default")
      (node (ref "R11") (pin "1") (pinfunction "1_1") (pintype "passive"))
      (node (ref "R12") (pin "2") (pinfunction "2_2") (pintype "passive"))
      (node (ref "U6") (pin "22") (pinfunction "ADC7_22") (pintype "input"))
    )
    (net (code "41") (name "/WAKE-UP") (class "Default")
      (node (ref "J12") (pin "2") (pinfunction "2_2") (pintype "power_in"))
      (node (ref "U3") (pin "C1") (pinfunction "VB_EN_C1") (pintype "power_in"))
      (node (ref "U6") (pin "26") (pinfunction "PC3_(ADC3/PCINT11)_26") (pintype "bidirectional"))
    )
    (net (code "42") (name "/XTAL1") (class "Default")
      (node (ref "C12") (pin "2") (pinfunction "2_2") (pintype "passive"))
      (node (ref "U6") (pin "7") (pinfunction "PB6_(PCINT6/XTAL1/TOSC1)_7") (pintype "bidirectional"))
      (node (ref "Y1") (pin "1") (pinfunction "1_1") (pintype "passive"))
    )
    (net (code "43") (name "/XTAL2") (class "Default")
      (node (ref "C13") (pin "2") (pinfunction "2_2") (pintype "passive"))
      (node (ref "U6") (pin "8") (pinfunction "PB7_(PCINT7/XTAL2/TOSC2)_8") (pintype "bidirectional"))
      (node (ref "Y1") (pin "2") (pinfunction "2_2") (pintype "passive"))
    )
    (net (code "44") (name "GND") (class "Default")
      (node (ref "C1") (pin "1") (pinfunction "1_1") (pintype "passive"))
      (node (ref "C10") (pin "-") (pinfunction "-_-") (pintype "passive"))
      (node (ref "C11") (pin "1") (pinfunction "1_1") (pintype "passive"))
      (node (ref "C12") (pin "1") (pinfunction "1_1") (pintype "passive"))
      (node (ref "C13") (pin "1") (pinfunction "1_1") (pintype "passive"))
      (node (ref "C14") (pin "1") (pinfunction "1_1") (pintype "passive"))
      (node (ref "C15") (pin "-") (pinfunction "-_-") (pintype "passive"))
      (node (ref "C16") (pin "1") (pinfunction "1_1") (pintype "passive"))
      (node (ref "C17") (pin "1") (pinfunction "1_1") (pintype "passive"))
      (node (ref "C18") (pin "-") (pinfunction "-_-") (pintype "passive"))
      (node (ref "C2") (pin "-") (pinfunction "-_-") (pintype "passive"))
      (node (ref "C20") (pin "-") (pinfunction "-_-") (pintype "passive"))
      (node (ref "C21") (pin "1") (pinfunction "1_1") (pintype "passive"))
      (node (ref "C22") (pin "-") (pinfunction "-_-") (pintype "passive"))
      (node (ref "C3") (pin "1") (pinfunction "1_1") (pintype "passive"))
      (node (ref "C4") (pin "1") (pinfunction "1_1") (pintype "passive"))
      (node (ref "C5") (pin "-") (pinfunction "-_-") (pintype "passive"))
      (node (ref "C6") (pin "1") (pinfunction "1_1") (pintype "passive"))
      (node (ref "C7") (pin "1") (pinfunction "1_1") (pintype "passive"))
      (node (ref "C8") (pin "2") (pinfunction "2_2") (pintype "passive"))
      (node (ref "C9") (pin "1") (pinfunction "1_1") (pintype "passive"))
      (node (ref "Cell1") (pin "3-") (pinfunction "Gnd_3-") (pintype "passive"))
      (node (ref "D1") (pin "1") (pinfunction "A_1") (pintype "passive"))
      (node (ref "D4") (pin "-") (pinfunction "-_-") (pintype "passive"))
      (node (ref "D5") (pin "-") (pinfunction "-_-") (pintype "passive"))
      (node (ref "D6") (pin "-") (pinfunction "-_-") (pintype "passive"))
      (node (ref "D8") (pin "-") (pinfunction "-_-") (pintype "passive"))
      (node (ref "J10") (pin "1") (pintype "power_in"))
      (node (ref "J9") (pin "1") (pintype "power_in"))
      (node (ref "P13") (pin "1") (pinfunction "1_1") (pintype "passive"))
      (node (ref "P14") (pin "1") (pinfunction "1_1") (pintype "passive"))
      (node (ref "P8") (pin "4") (pinfunction "4_4") (pintype "passive"))
      (node (ref "R12") (pin "1") (pinfunction "1_1") (pintype "passive"))
      (node (ref "R27") (pin "1") (pinfunction "1_1") (pintype "passive"))
      (node (ref "R32") (pin "1") (pinfunction "1_1") (pintype "passive"))
      (node (ref "R5") (pin "1") (pinfunction "1_1") (pintype "passive"))
      (node (ref "S1") (pin "1") (pinfunction "A0_1") (pintype "passive"))
      (node (ref "S1") (pin "2") (pinfunction "A1_2") (pintype "passive"))
      (node (ref "S2") (pin "3") (pinfunction "B0_3") (pintype "passive"))
      (node (ref "S3") (pin "3") (pinfunction "B0_3") (pintype "passive"))
      (node (ref "S4") (pin "3") (pinfunction "B0_3") (pintype "passive"))
      (node (ref "S5") (pin "3") (pinfunction "B0_3") (pintype "passive"))
      (node (ref "S6") (pin "3") (pinfunction "B0_3") (pintype "passive"))
      (node (ref "S7") (pin "2") (pinfunction "B0_2") (pintype "passive"))
      (node (ref "S8") (pin "2") (pinfunction "B0_2") (pintype "passive"))
      (node (ref "U1") (pin "6") (pinfunction "GND_6") (pintype "power_in"))
      (node (ref "U10") (pin "2") (pinfunction "Solar-_2") (pintype "power_in"))
      (node (ref "U11") (pin "2") (pinfunction "GND_2") (pintype "power_in"))
      (node (ref "U12") (pin "3") (pinfunction "GND_3") (pintype "passive"))
      (node (ref "U13") (pin "5") (pinfunction "GND_5") (pintype "power_in"))
      (node (ref "U14") (pin "2") (pinfunction "GND_2") (pintype "power_in"))
      (node (ref "U15") (pin "1") (pinfunction "GND_1") (pintype "power_in"))
      (node (ref "U16") (pin "1") (pinfunction "GND_1") (pintype "power_in"))
      (node (ref "U17") (pin "1") (pinfunction "GND_1") (pintype "power_in"))
      (node (ref "U18") (pin "1") (pinfunction "GND_1") (pintype "power_in"))
      (node (ref "U19") (pin "GND") (pinfunction "GND_GND") (pintype "power_in"))
      (node (ref "U2") (pin "4") (pinfunction "GND_4") (pintype "passive"))
      (node (ref "U3") (pin "C2") (pinfunction "GND_C2") (pintype "power_in"))
      (node (ref "U4") (pin "2") (pinfunction "Solar-_2") (pintype "power_in"))
      (node (ref "U5") (pin "1") (pinfunction "A0_1") (pintype "passive"))
      (node (ref "U5") (pin "2") (pinfunction "A1_2") (pintype "passive"))
      (node (ref "U5") (pin "3") (pinfunction "A2_3") (pintype "passive"))
      (node (ref "U5") (pin "4") (pinfunction "Vss_4") (pintype "passive"))
      (node (ref "U6") (pin "21") (pinfunction "GND_21") (pintype "power_in"))
      (node (ref "U6") (pin "3") (pinfunction "GND_3") (pintype "power_in"))
      (node (ref "U6") (pin "5") (pinfunction "GND_5") (pintype "power_in"))
      (node (ref "U7") (pin "OUT-") (pinfunction "OUT-_OUT-") (pintype "power_in"))
      (node (ref "X1") (pin "9") (pinfunction "GND_9") (pintype "power_in"))
    )
    (net (code "45") (name "Net-(C4-Pad2)") (class "Default")
      (node (ref "C4") (pin "2") (pinfunction "2_2") (pintype "passive"))
      (node (ref "P3") (pin "1") (pinfunction "1_1") (pintype "passive"))
      (node (ref "R2") (pin "2") (pinfunction "2_2") (pintype "passive"))
    )
    (net (code "46") (name "Net-(D1-K)") (class "Default")
      (node (ref "D1") (pin "2") (pinfunction "K_2") (pintype "passive"))
      (node (ref "J3") (pin "1") (pinfunction "1_1") (pintype "power_in"))
      (node (ref "R1") (pin "1") (pinfunction "1_1") (pintype "passive"))
      (node (ref "R2") (pin "1") (pinfunction "1_1") (pintype "passive"))
      (node (ref "U1") (pin "12") (pinfunction "SENSE+_12") (pintype "power_in"))
    )
    (net (code "47") (name "Net-(D2-Pad+)") (class "Default")
      (node (ref "D2") (pin "+") (pinfunction "+_+") (pintype "passive"))
      (node (ref "R3") (pin "2") (pinfunction "2_2") (pintype "passive"))
    )
    (net (code "48") (name "Net-(D4-Pad+)") (class "Default")
      (node (ref "D4") (pin "+") (pinfunction "+_+") (pintype "passive"))
      (node (ref "R9") (pin "2") (pinfunction "2_2") (pintype "passive"))
    )
    (net (code "49") (name "Net-(D5-Pad+)") (class "Default")
      (node (ref "D5") (pin "+") (pinfunction "+_+") (pintype "passive"))
      (node (ref "R10") (pin "1") (pinfunction "1_1") (pintype "passive"))
    )
    (net (code "50") (name "Net-(D6-Pad+)") (class "Default")
      (node (ref "D6") (pin "+") (pinfunction "+_+") (pintype "passive"))
      (node (ref "R21") (pin "1") (pinfunction "1_1") (pintype "passive"))
    )
    (net (code "51") (name "Net-(D7-Pad+)") (class "Default")
      (node (ref "D7") (pin "+") (pinfunction "+_+") (pintype "passive"))
      (node (ref "R24") (pin "1") (pinfunction "1_1") (pintype "passive"))
    )
    (net (code "52") (name "Net-(D8-Pad+)") (class "Default")
      (node (ref "D8") (pin "+") (pinfunction "+_+") (pintype "passive"))
      (node (ref "R31") (pin "1") (pinfunction "1_1") (pintype "passive"))
    )
    (net (code "53") (name "Net-(J1-Pad1)") (class "Default")
      (node (ref "J1") (pin "1") (pinfunction "1_1") (pintype "passive"))
      (node (ref "P3") (pin "5") (pinfunction "5_5") (pintype "passive"))
    )
    (net (code "54") (name "Net-(J5-Pad1)") (class "Default")
      (node (ref "J5") (pin "1") (pinfunction "1_1") (pintype "power_in"))
      (node (ref "R10") (pin "2") (pinfunction "2_2") (pintype "passive"))
    )
    (net (code "55") (name "Net-(P12-Pad3)") (class "Default")
      (node (ref "P12") (pin "3") (pinfunction "3_3") (pintype "passive"))
      (node (ref "R23") (pin "2") (pinfunction "2_2") (pintype "passive"))
    )
    (net (code "56") (name "Net-(P15-T+)") (class "Default")
      (node (ref "C19") (pin "2") (pinfunction "2_2") (pintype "passive"))
      (node (ref "P15") (pin "2") (pinfunction "T+_2") (pintype "power_in"))
      (node (ref "U18") (pin "3") (pinfunction "T+_3") (pintype "power_in"))
    )
    (net (code "57") (name "Net-(P15-T-)") (class "Default")
      (node (ref "C19") (pin "1") (pinfunction "1_1") (pintype "passive"))
      (node (ref "P15") (pin "1") (pinfunction "T-_1") (pintype "power_in"))
      (node (ref "U18") (pin "2") (pinfunction "T-_2") (pintype "power_in"))
    )
    (net (code "58") (name "Net-(R30-Pad1)") (class "Default")
      (node (ref "R30") (pin "1") (pinfunction "1_1") (pintype "passive"))
      (node (ref "R32") (pin "2") (pinfunction "2_2") (pintype "passive"))
    )
    (net (code "59") (name "Net-(U1-ADR0)") (class "Default")
      (node (ref "J10") (pin "2") (pinfunction "2_2") (pintype "power_in"))
      (node (ref "U1") (pin "4") (pinfunction "ADR0_4") (pintype "power_in"))
    )
    (net (code "60") (name "Net-(U1-ADR1)") (class "Default")
      (node (ref "J9") (pin "2") (pinfunction "2_2") (pintype "power_in"))
      (node (ref "U1") (pin "3") (pinfunction "ADR1_3") (pintype "power_in"))
    )
    (net (code "61") (name "Net-(U1-SDAO)") (class "Default")
      (node (ref "J11") (pin "1") (pintype "power_in"))
      (node (ref "U1") (pin "9") (pinfunction "SDAO_9") (pintype "power_in"))
    )
    (net (code "62") (name "Net-(U1-SENSE-)") (class "Default")
      (node (ref "J4") (pin "2") (pinfunction "2_2") (pintype "power_in"))
      (node (ref "R1") (pin "2") (pinfunction "2_2") (pintype "passive"))
      (node (ref "U1") (pin "11") (pinfunction "SENSE-_11") (pintype "power_in"))
    )
    (net (code "63") (name "Net-(U1-VDD)") (class "Default")
      (node (ref "C3") (pin "2") (pinfunction "2_2") (pintype "passive"))
      (node (ref "P3") (pin "2") (pinfunction "2_2") (pintype "passive"))
      (node (ref "P3") (pin "4") (pinfunction "4_4") (pintype "passive"))
      (node (ref "P3") (pin "6") (pinfunction "6_6") (pintype "passive"))
      (node (ref "U1") (pin "1") (pinfunction "VDD_1") (pintype "power_in"))
    )
    (net (code "64") (name "Net-(U2-VBAT)") (class "Default")
      (node (ref "Cell1") (pin "1+") (pinfunction "+Ve_1+") (pintype "passive"))
      (node (ref "Cell1") (pin "2+") (pinfunction "+Ve_2+") (pintype "passive"))
      (node (ref "U2") (pin "3") (pinfunction "VBAT_3") (pintype "power_in"))
    )
    (net (code "65") (name "Net-(U2-X1)") (class "Default")
      (node (ref "Q1") (pin "1") (pinfunction "1_1") (pintype "passive"))
      (node (ref "U2") (pin "1") (pinfunction "X1_1") (pintype "input"))
    )
    (net (code "66") (name "Net-(U2-X2)") (class "Default")
      (node (ref "Q1") (pin "2") (pinfunction "2_2") (pintype "passive"))
      (node (ref "U2") (pin "2") (pinfunction "X2_2") (pintype "output"))
    )
    (net (code "67") (name "Net-(U6-AREF)") (class "Default")
      (node (ref "C9") (pin "2") (pinfunction "2_2") (pintype "passive"))
      (node (ref "U6") (pin "20") (pinfunction "AREF_20") (pintype "passive"))
    )
    (net (code "68") (name "Net-(U10-Solar+)") (class "Default")
      (node (ref "F1") (pin "2") (pinfunction "2_2") (pintype "passive"))
      (node (ref "U10") (pin "1") (pinfunction "Solar+_1") (pintype "power_in"))
    )
    (net (code "69") (name "Net-(U11-DC-Out)") (class "Default")
      (node (ref "J6") (pin "1") (pinfunction "1_1") (pintype "power_in"))
      (node (ref "U11") (pin "4") (pinfunction "DC-Out_4") (pintype "power_in"))
    )
    (net (code "70") (name "Net-(U13-FILTER)") (class "Default")
      (node (ref "C14") (pin "2") (pinfunction "2_2") (pintype "passive"))
      (node (ref "U13") (pin "6") (pinfunction "FILTER_6") (pintype "passive"))
    )
    (net (code "71") (name "Net-(U13-I+_0)") (class "Default")
      (node (ref "J7") (pin "2") (pinfunction "2_2") (pintype "power_in"))
      (node (ref "U13") (pin "1") (pinfunction "I+_0_1") (pintype "passive"))
      (node (ref "U13") (pin "2") (pinfunction "I+_1_2") (pintype "passive"))
    )
    (net (code "72") (name "Net-(U13-I-_0)") (class "Default")
      (node (ref "J8") (pin "2") (pinfunction "2_2") (pintype "power_in"))
      (node (ref "U13") (pin "3") (pinfunction "I-_0_3") (pintype "passive"))
      (node (ref "U13") (pin "4") (pinfunction "I-_1_4") (pintype "passive"))
    )
    (net (code "73") (name "Net-(X1-RXD)") (class "Default")
      (node (ref "R23") (pin "1") (pinfunction "1_1") (pintype "passive"))
      (node (ref "R30") (pin "2") (pinfunction "2_2") (pintype "passive"))
      (node (ref "X1") (pin "15") (pinfunction "RXD_15") (pintype "passive"))
    )
    (net (code "74") (name "Net-(X1-TXD)") (class "Default")
      (node (ref "P12") (pin "1") (pinfunction "1_1") (pintype "passive"))
      (node (ref "X1") (pin "16") (pinfunction "TXD_16") (pintype "output"))
    )
    (net (code "75") (name "VCC-3V3") (class "Default")
      (node (ref "C17") (pin "2") (pinfunction "2_2") (pintype "passive"))
      (node (ref "C18") (pin "+") (pinfunction "+_+") (pintype "passive"))
      (node (ref "R21") (pin "2") (pinfunction "2_2") (pintype "passive"))
      (node (ref "R24") (pin "2") (pinfunction "2_2") (pintype "passive"))
      (node (ref "R25") (pin "2") (pinfunction "2_2") (pintype "passive"))
      (node (ref "R26") (pin "2") (pinfunction "2_2") (pintype "passive"))
      (node (ref "R33") (pin "2") (pinfunction "2_2") (pintype "passive"))
      (node (ref "U17") (pin "2") (pinfunction "Vout_2") (pintype "power_in"))
      (node (ref "X1") (pin "8") (pinfunction "VCC_8") (pintype "power_in"))
    )
    (net (code "76") (name "VCC-5V") (class "Default")
      (node (ref "C10") (pin "+") (pinfunction "+_+") (pintype "passive"))
      (node (ref "C11") (pin "2") (pinfunction "2_2") (pintype "passive"))
      (node (ref "C15") (pin "+") (pinfunction "+_+") (pintype "passive"))
      (node (ref "C16") (pin "2") (pinfunction "2_2") (pintype "passive"))
      (node (ref "C22") (pin "+") (pinfunction "+_+") (pintype "passive"))
      (node (ref "C7") (pin "2") (pinfunction "2_2") (pintype "passive"))
      (node (ref "J10") (pin "3") (pinfunction "3_3") (pintype "power_in"))
      (node (ref "J12") (pin "1") (pintype "power_in"))
      (node (ref "J5") (pin "2") (pinfunction "2_2") (pintype "power_in"))
      (node (ref "J9") (pin "3") (pinfunction "3_3") (pintype "power_in"))
      (node (ref "P3") (pin "3") (pinfunction "3_3") (pintype "passive"))
      (node (ref "P8") (pin "6") (pinfunction "6_6") (pintype "passive"))
      (node (ref "R3") (pin "1") (pinfunction "1_1") (pintype "passive"))
      (node (ref "R4") (pin "2") (pinfunction "2_2") (pintype "passive"))
      (node (ref "R7") (pin "2") (pinfunction "2_2") (pintype "passive"))
      (node (ref "R8") (pin "2") (pinfunction "2_2") (pintype "passive"))
      (node (ref "U1") (pin "2") (pinfunction "INTVcc_2") (pintype "power_in"))
      (node (ref "U13") (pin "8") (pinfunction "VCC_8") (pintype "power_in"))
      (node (ref "U3") (pin "A1") (pinfunction "VIN_A1") (pintype "power_in"))
      (node (ref "U3") (pin "B1") (pinfunction "VIN_B1") (pintype "power_in"))
      (node (ref "U6") (pin "18") (pinfunction "AVCC_18") (pintype "power_in"))
      (node (ref "U6") (pin "4") (pinfunction "VCC_4") (pintype "power_in"))
      (node (ref "U6") (pin "6") (pinfunction "VCC_6") (pintype "power_in"))
      (node (ref "U7") (pin "OUT+") (pinfunction "OUT+_OUT+") (pintype "power_in"))
    )
    (net (code "77") (name "VCC-5V-EN") (class "Default")
      (node (ref "C1") (pin "2") (pinfunction "2_2") (pintype "passive"))
      (node (ref "C2") (pin "+") (pinfunction "+_+") (pintype "passive"))
      (node (ref "C20") (pin "+") (pinfunction "+_+") (pintype "passive"))
      (node (ref "C21") (pin "2") (pinfunction "2_2") (pintype "passive"))
      (node (ref "C5") (pin "+") (pinfunction "+_+") (pintype "passive"))
      (node (ref "C6") (pin "2") (pinfunction "2_2") (pintype "passive"))
      (node (ref "D3") (pin "2") (pinfunction "K_2") (pintype "passive"))
      (node (ref "J12") (pin "3") (pinfunction "3_3") (pintype "power_in"))
      (node (ref "R13") (pin "2") (pinfunction "2_2") (pintype "passive"))
      (node (ref "R14") (pin "2") (pinfunction "2_2") (pintype "passive"))
      (node (ref "R15") (pin "2") (pinfunction "2_2") (pintype "passive"))
      (node (ref "R16") (pin "2") (pinfunction "2_2") (pintype "passive"))
      (node (ref "R17") (pin "2") (pinfunction "2_2") (pintype "passive"))
      (node (ref "R18") (pin "1") (pinfunction "1_1") (pintype "passive"))
      (node (ref "R19") (pin "1") (pinfunction "1_1") (pintype "passive"))
      (node (ref "R20") (pin "2") (pinfunction "2_2") (pintype "passive"))
      (node (ref "R28") (pin "1") (pinfunction "1_1") (pintype "passive"))
      (node (ref "R29") (pin "1") (pinfunction "1_1") (pintype "passive"))
      (node (ref "R31") (pin "2") (pinfunction "2_2") (pintype "passive"))
      (node (ref "R6") (pin "1") (pinfunction "1_1") (pintype "passive"))
      (node (ref "U14") (pin "1") (pinfunction "VCC_1") (pintype "power_in"))
      (node (ref "U15") (pin "3") (pinfunction "VDD_3") (pintype "power_in"))
      (node (ref "U16") (pin "3") (pinfunction "VDD_3") (pintype "power_in"))
      (node (ref "U17") (pin "3") (pinfunction "Vin_3") (pintype "power_in"))
      (node (ref "U18") (pin "4") (pinfunction "Vcc_4") (pintype "power_in"))
      (node (ref "U19") (pin "VDD") (pinfunction "VDD_VDD") (pintype "power_in"))
      (node (ref "U2") (pin "8") (pinfunction "VCC_8") (pintype "power_in"))
      (node (ref "U3") (pin "A2") (pinfunction "VOUT_A2") (pintype "power_in"))
      (node (ref "U3") (pin "B2") (pinfunction "VOUT_B2") (pintype "power_in"))
      (node (ref "U5") (pin "8") (pinfunction "VCC_8") (pintype "passive"))
    )
    (net (code "78") (name "unconnected-(J11-Pad3)") (class "Default")
      (node (ref "J11") (pin "3") (pinfunction "3_3") (pintype "power_in+no_connect"))
    )
    (net (code "79") (name "unconnected-(S2-A0-Pad1)") (class "Default")
      (node (ref "S2") (pin "1") (pinfunction "A0_1") (pintype "passive"))
    )
    (net (code "80") (name "unconnected-(S2-B1-Pad4)") (class "Default")
      (node (ref "S2") (pin "4") (pinfunction "B1_4") (pintype "passive"))
    )
    (net (code "81") (name "unconnected-(S3-A0-Pad1)") (class "Default")
      (node (ref "S3") (pin "1") (pinfunction "A0_1") (pintype "passive"))
    )
    (net (code "82") (name "unconnected-(S3-B1-Pad4)") (class "Default")
      (node (ref "S3") (pin "4") (pinfunction "B1_4") (pintype "passive"))
    )
    (net (code "83") (name "unconnected-(S4-A0-Pad1)") (class "Default")
      (node (ref "S4") (pin "1") (pinfunction "A0_1") (pintype "passive"))
    )
    (net (code "84") (name "unconnected-(S4-B1-Pad4)") (class "Default")
      (node (ref "S4") (pin "4") (pinfunction "B1_4") (pintype "passive"))
    )
    (net (code "85") (name "unconnected-(S5-A0-Pad1)") (class "Default")
      (node (ref "S5") (pin "1") (pinfunction "A0_1") (pintype "passive"))
    )
    (net (code "86") (name "unconnected-(S5-B1-Pad4)") (class "Default")
      (node (ref "S5") (pin "4") (pinfunction "B1_4") (pintype "passive"))
    )
    (net (code "87") (name "unconnected-(S6-A0-Pad1)") (class "Default")
      (node (ref "S6") (pin "1") (pinfunction "A0_1") (pintype "passive"))
    )
    (net (code "88") (name "unconnected-(S6-B1-Pad4)") (class "Default")
      (node (ref "S6") (pin "4") (pinfunction "B1_4") (pintype "passive"))
    )
    (net (code "89") (name "unconnected-(S7-A0-Pad1)") (class "Default")
      (node (ref "S7") (pin "1") (pinfunction "A0_1") (pintype "passive"))
    )
    (net (code "90") (name "unconnected-(S7-B1-Pad3)") (class "Default")
      (node (ref "S7") (pin "3") (pinfunction "B1_3") (pintype "passive"))
    )
    (net (code "91") (name "unconnected-(S8-A0-Pad1)") (class "Default")
      (node (ref "S8") (pin "1") (pinfunction "A0_1") (pintype "passive"))
    )
    (net (code "92") (name "unconnected-(S8-B1-Pad3)") (class "Default")
      (node (ref "S8") (pin "3") (pinfunction "B1_3") (pintype "passive"))
    )
    (net (code "93") (name "unconnected-(U2-SQW{slash}OUT-Pad7)") (class "Default")
      (node (ref "U2") (pin "7") (pinfunction "SQW/OUT_7") (pintype "output+no_connect"))
    )
    (net (code "94") (name "unconnected-(U5-WP-Pad7)") (class "Default")
      (node (ref "U5") (pin "7") (pinfunction "WP_7") (pintype "passive+no_connect"))
    )
    (net (code "95") (name "unconnected-(U12-QST-Pad5)") (class "Default")
      (node (ref "U12") (pin "5") (pinfunction "QST_5") (pintype "passive+no_connect"))
    )
    (net (code "96") (name "unconnected-(U18-N.C.-Pad8)") (class "Default")
      (node (ref "U18") (pin "8") (pinfunction "N.C._8") (pintype "power_in+no_connect"))
    )
    (net (code "97") (name "unconnected-(U19-PadNC)") (class "Default")
      (node (ref "U19") (pin "NC") (pinfunction "NC_NC") (pintype "power_in+no_connect"))
    )
    (net (code "98") (name "unconnected-(X1-ADC-Pad2)") (class "Default")
      (node (ref "X1") (pin "2") (pinfunction "ADC_2") (pintype "passive"))
    )
    (net (code "99") (name "unconnected-(X1-GPIO4-Pad14)") (class "Default")
      (node (ref "X1") (pin "14") (pinfunction "GPIO4_14") (pintype "passive"))
    )
    (net (code "100") (name "unconnected-(X1-GPIO5-Pad13)") (class "Default")
      (node (ref "X1") (pin "13") (pinfunction "GPIO5_13") (pintype "passive"))
    )
    (net (code "101") (name "unconnected-(X1-GPIO12-Pad6)") (class "Default")
      (node (ref "X1") (pin "6") (pinfunction "GPIO12_6") (pintype "passive"))
    )
    (net (code "102") (name "unconnected-(X1-GPIO13-Pad7)") (class "Default")
      (node (ref "X1") (pin "7") (pinfunction "GPIO13_7") (pintype "passive"))
    )
    (net (code "103") (name "unconnected-(X1-GPIO14-Pad5)") (class "Default")
      (node (ref "X1") (pin "5") (pinfunction "GPIO14_5") (pintype "passive"))
    )
    (net (code "104") (name "unconnected-(X1-GPIO16-Pad4)") (class "Default")
      (node (ref "X1") (pin "4") (pinfunction "GPIO16_4") (pintype "passive"))
    )
  )
)
